# Wireless_thermometer_BLE_module.net
KiCad netlist of a schematic drawn in Altium Designer
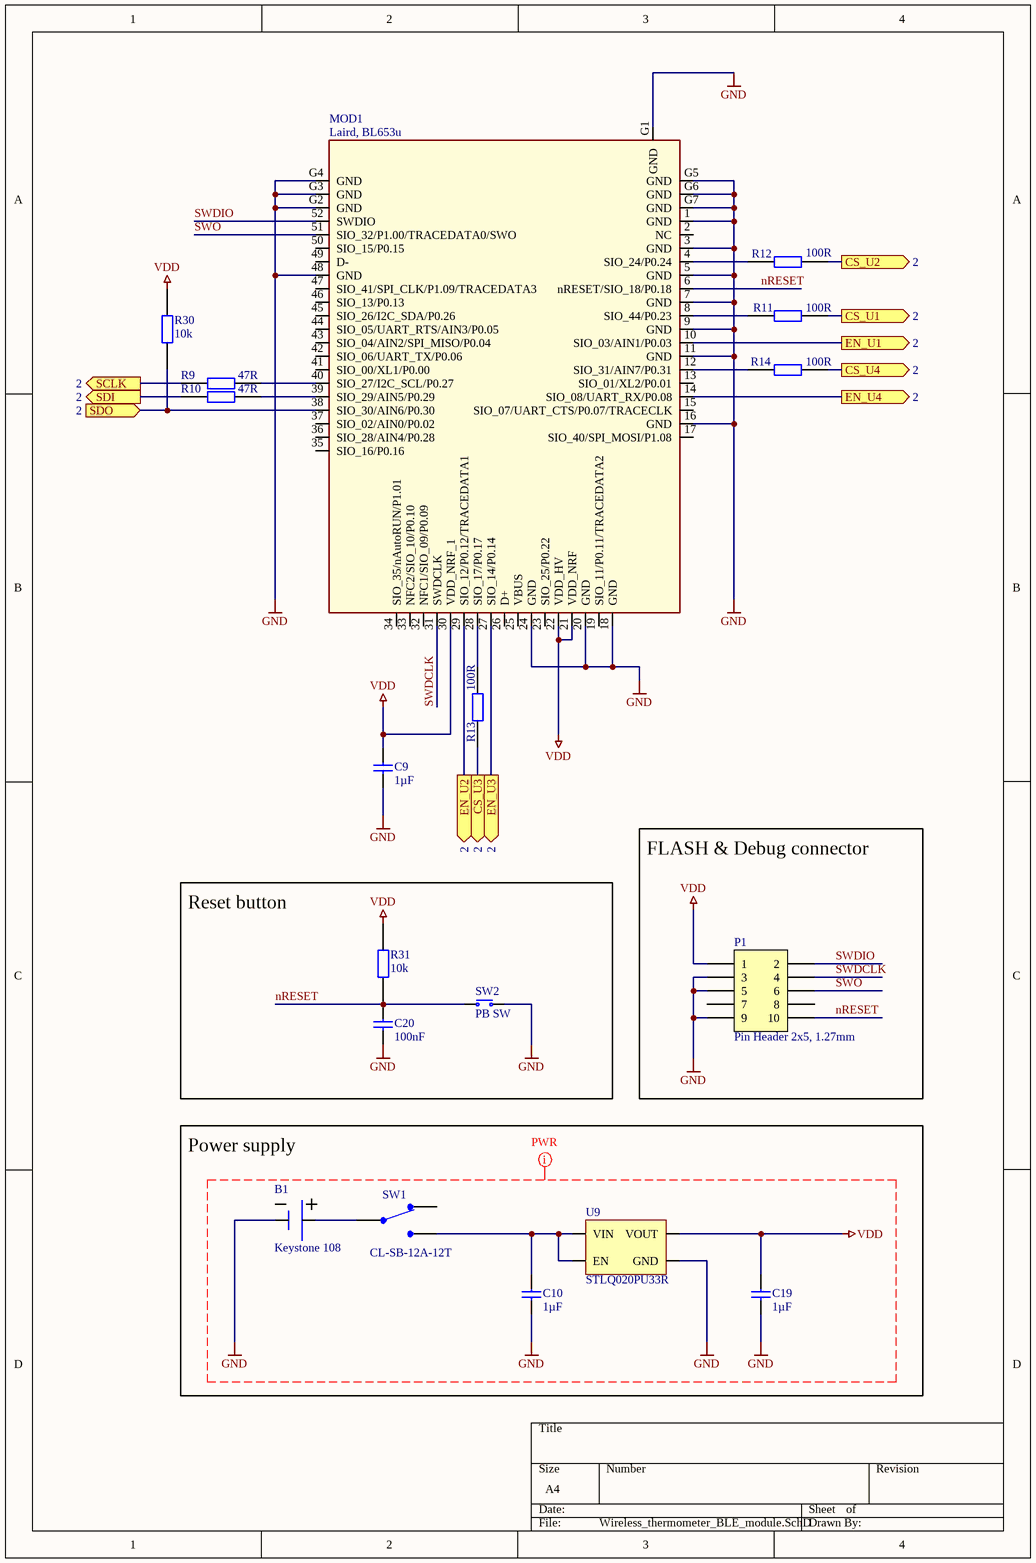
[diagram p0: Wireless_thermometer_BLE_module.SchDoc]

(export (version "E")
  (design (tool "Eeschema 10.0.6"))
  (components
    (comp (ref "B1")
      (value "Keystone 108")
      (footprint "Keystone 108")
      (description "Tip Plg 108 Phe Bagged NKL#9HHS108")
      (fields
        (field (name "MANUFACTURER") "Keystone Electronics")
        (field (name "MANUFACTURER PART NUMBER") "108")
      )
      (libsource (lib "Remote_thermometer") (part "Keystone 108"))
    )
    (comp (ref "C9")
      (value "1µF")
      (footprint "CAPC1005X04L")
      (description "Capacitor, X7R, ±10%")
      (fields (field (name "PART NUMBER") "C0402-1µ0") (field (name "PUBLISHER") "Nordic Semiconductor"))
      (libsource (lib "Remote_thermometer") (part "CAP_0402"))
    )
    (comp (ref "C10")
      (value "1µF")
      (footprint "CAPC1005X04L")
      (description "Capacitor, X7R, ±10%")
      (fields (field (name "PART NUMBER") "C0402-1µ0") (field (name "PUBLISHER") "Nordic Semiconductor"))
      (libsource (lib "Remote_thermometer") (part "CAP_0402"))
    )
    (comp (ref "C19")
      (value "1µF")
      (footprint "CAPC1005X04L")
      (description "Capacitor, X7R, ±10%")
      (fields (field (name "PART NUMBER") "C0402-1µ0") (field (name "PUBLISHER") "Nordic Semiconductor"))
      (libsource (lib "Remote_thermometer") (part "CAP_0402"))
    )
    (comp (ref "C20")
      (value "100nF")
      (footprint "CAPC1005X04L")
      (description "Capacitor, X7R, ±10%")
      (fields (field (name "PART NUMBER") "C0402-1µ0") (field (name "PUBLISHER") "Nordic Semiconductor"))
      (libsource (lib "Remote_thermometer") (part "CAP_0402"))
    )
    (comp (ref "MOD1")
      (value "Laird, BL653u")
      (footprint "Laird, BL653u")
      (description "BL653µ Integrated Antenna module, 453-00059")
      (fields (field (name "MANUFACTURER PART NUMBER") "453-00059") (field (name "MANUFACTURER") "Laird"))
      (libsource (lib "Remote_thermometer") (part "Laird, BL653u"))
    )
    (comp (ref "P1")
      (value "Pin Header 2x5, 1.27mm")
      (footprint "HDR_2x5-SMD-1.27mm-K")
      (description "Pin Header 2x5, 1.27mm (50mil), SMD, Keying Shroud")
      (fields
        (field (name "PART NUMBER") "Pin Header 2x5 SMD, 1.27mm, KS")
        (field (name "MANUFACTURER") "W-CON")
        (field (name "PUBLISHER") "Nordic Semiconductor")
      )
      (libsource (lib "Remote_thermometer") (part "Pin Header 2x5 SMD, 1.27mm, KS"))
    )
    (comp (ref "R9")
      (value "47R")
      (footprint "RESC1005X04L")
      (description "Resistor")
      (fields (field (name "PART NUMBER") "R0603-430R") (field (name "PUBLISHER") "Nordic Semiconductor"))
      (libsource (lib "Remote_thermometer") (part "RES_0402"))
    )
    (comp (ref "R10")
      (value "47R")
      (footprint "RESC1005X04L")
      (description "Resistor")
      (fields (field (name "PART NUMBER") "R0603-430R") (field (name "PUBLISHER") "Nordic Semiconductor"))
      (libsource (lib "Remote_thermometer") (part "RES_0402"))
    )
    (comp (ref "R11")
      (value "100R")
      (footprint "RESC1005X04L")
      (description "Resistor")
      (fields (field (name "PART NUMBER") "R0603-430R") (field (name "PUBLISHER") "Nordic Semiconductor"))
      (libsource (lib "Remote_thermometer") (part "RES_0402"))
    )
    (comp (ref "R12")
      (value "100R")
      (footprint "RESC1005X04L")
      (description "Resistor")
      (fields (field (name "PART NUMBER") "R0603-430R") (field (name "PUBLISHER") "Nordic Semiconductor"))
      (libsource (lib "Remote_thermometer") (part "RES_0402"))
    )
    (comp (ref "R13")
      (value "100R")
      (footprint "RESC1005X04L")
      (description "Resistor")
      (fields (field (name "PART NUMBER") "R0603-430R") (field (name "PUBLISHER") "Nordic Semiconductor"))
      (libsource (lib "Remote_thermometer") (part "RES_0402"))
    )
    (comp (ref "R14")
      (value "100R")
      (footprint "RESC1005X04L")
      (description "Resistor")
      (fields (field (name "PART NUMBER") "R0603-430R") (field (name "PUBLISHER") "Nordic Semiconductor"))
      (libsource (lib "Remote_thermometer") (part "RES_0402"))
    )
    (comp (ref "R30")
      (value "10k")
      (footprint "RESC1005X04L")
      (description "Resistor")
      (fields (field (name "PART NUMBER") "R0603-430R") (field (name "PUBLISHER") "Nordic Semiconductor"))
      (libsource (lib "Remote_thermometer") (part "RES_0402"))
    )
    (comp (ref "R31")
      (value "10k")
      (footprint "RESC1005X04L")
      (description "Resistor")
      (fields (field (name "PART NUMBER") "R0603-430R") (field (name "PUBLISHER") "Nordic Semiconductor"))
      (libsource (lib "Remote_thermometer") (part "RES_0402"))
    )
    (comp (ref "SW1")
      (value "CL-SB-12A-12T")
      (footprint "CL-SB-12A-12T")
      (description "Slide Switch, 2 Positions, SPDT, Latched, 0.2A, 12VDC, Solder Terminal, Through Hole-right Angle")
      (fields (field (name "MANUFACTURER") "Nidec Copal"))
      (libsource (lib "Remote_thermometer") (part "CL-SB-12A-12T"))
    )
    (comp (ref "SW2")
      (value "PB SW")
      (footprint "C&K_PTS810")
      (description "Tactile Switch, SPNO, SMD, 260gf, 4.2x3.2x2.5mm")
      (fields
        (field (name "PART NUMBER") "PTS810 SJK 250 SMTR LFS")
        (field (name "MANUFACTURER") "C&K Components")
        (field (name "PUBLISHER") "Nordic Semiconductor")
      )
      (libsource (lib "Remote_thermometer") (part "PTS810 SJK 250 SMTR LFS"))
    )
    (comp (ref "U9")
      (value "STLQ020PU33R")
      (footprint "STLQ020PU33R")
      (description "Ldo, Fixed, 3.3V, 0.2A, -40 to 125DEG C;")
      (fields (field (name "MANUFACTURER") "STMicroelectronics"))
      (libsource (lib "Remote_thermometer") (part "STLQ020PU33R"))
    )
  )
  (nets
    (net (code "1") (name "/CS_U1") (class "Default")
      (node (ref "R11") (pin "2") (pinfunction "2_2") (pintype "passive"))
    )
    (net (code "2") (name "/CS_U2") (class "Default")
      (node (ref "R12") (pin "2") (pinfunction "2_2") (pintype "passive"))
    )
    (net (code "3") (name "/CS_U3") (class "Default")
      (node (ref "R13") (pin "2") (pinfunction "2_2") (pintype "passive"))
    )
    (net (code "4") (name "/CS_U4") (class "Default")
      (node (ref "R14") (pin "2") (pinfunction "2_2") (pintype "passive"))
    )
    (net (code "5") (name "/EN_U1") (class "Default")
      (node (ref "MOD1") (pin "10") (pinfunction "SIO_03/AIN1/P0.03_10") (pintype "passive"))
    )
    (net (code "6") (name "/EN_U2") (class "Default")
      (node (ref "MOD1") (pin "29") (pinfunction "SIO_12/P0.12/TRACEDATA1_29") (pintype "passive"))
    )
    (net (code "7") (name "/EN_U3") (class "Default")
      (node (ref "MOD1") (pin "27") (pinfunction "SIO_14/P0.14_27") (pintype "passive"))
    )
    (net (code "8") (name "/EN_U4") (class "Default")
      (node (ref "MOD1") (pin "14") (pinfunction "SIO_08/UART_RX/P0.08_14") (pintype "passive"))
    )
    (net (code "9") (name "/SCLK") (class "Default")
      (node (ref "R9") (pin "1") (pinfunction "1_1") (pintype "passive"))
    )
    (net (code "10") (name "/SDI") (class "Default")
      (node (ref "R10") (pin "1") (pinfunction "1_1") (pintype "passive"))
    )
    (net (code "11") (name "/SDO") (class "Default")
      (node (ref "MOD1") (pin "38") (pinfunction "SIO_30/AIN6/P0.30_38") (pintype "passive"))
      (node (ref "R30") (pin "1") (pinfunction "1_1") (pintype "passive"))
    )
    (net (code "12") (name "/SWDCLK") (class "Default")
      (node (ref "MOD1") (pin "31") (pinfunction "SWDCLK_31") (pintype "passive"))
      (node (ref "P1") (pin "4") (pinfunction "4_4") (pintype "passive"))
    )
    (net (code "13") (name "/SWDIO") (class "Default")
      (node (ref "MOD1") (pin "52") (pinfunction "SWDIO_52") (pintype "passive"))
      (node (ref "P1") (pin "2") (pinfunction "2_2") (pintype "passive"))
    )
    (net (code "14") (name "/SWO") (class "Default")
      (node (ref "MOD1") (pin "51") (pinfunction "SIO_32/P1.00/TRACEDATA0/SWO_51") (pintype "passive"))
      (node (ref "P1") (pin "6") (pinfunction "6_6") (pintype "passive"))
    )
    (net (code "15") (name "/nRESET") (class "Default")
      (node (ref "C20") (pin "2") (pinfunction "2_2") (pintype "passive"))
      (node (ref "MOD1") (pin "6") (pinfunction "nRESET/SIO_18/P0.18_6") (pintype "passive"))
      (node (ref "P1") (pin "10") (pinfunction "10_10") (pintype "passive"))
      (node (ref "R31") (pin "1") (pinfunction "1_1") (pintype "passive"))
      (node (ref "SW2") (pin "2") (pinfunction "COM_2") (pintype "passive"))
    )
    (net (code "16") (name "GND") (class "Default")
      (node (ref "B1") (pin "2") (pinfunction "2_2") (pintype "passive"))
      (node (ref "C10") (pin "1") (pinfunction "1_1") (pintype "passive"))
      (node (ref "C19") (pin "1") (pinfunction "1_1") (pintype "passive"))
      (node (ref "C20") (pin "1") (pinfunction "1_1") (pintype "passive"))
      (node (ref "C9") (pin "1") (pinfunction "1_1") (pintype "passive"))
      (node (ref "MOD1") (pin "1") (pinfunction "GND_1") (pintype "passive"))
      (node (ref "MOD1") (pin "11") (pinfunction "GND_11") (pintype "passive"))
      (node (ref "MOD1") (pin "16") (pinfunction "GND_16") (pintype "passive"))
      (node (ref "MOD1") (pin "18") (pinfunction "GND_18") (pintype "passive"))
      (node (ref "MOD1") (pin "20") (pinfunction "GND_20") (pintype "passive"))
      (node (ref "MOD1") (pin "24") (pinfunction "GND_24") (pintype "passive"))
      (node (ref "MOD1") (pin "3") (pinfunction "GND_3") (pintype "passive"))
      (node (ref "MOD1") (pin "48") (pinfunction "GND_48") (pintype "passive"))
      (node (ref "MOD1") (pin "5") (pinfunction "GND_5") (pintype "passive"))
      (node (ref "MOD1") (pin "7") (pinfunction "GND_7") (pintype "passive"))
      (node (ref "MOD1") (pin "9") (pinfunction "GND_9") (pintype "passive"))
      (node (ref "MOD1") (pin "G1") (pinfunction "GND_G1") (pintype "passive"))
      (node (ref "MOD1") (pin "G2") (pinfunction "GND_G2") (pintype "passive"))
      (node (ref "MOD1") (pin "G3") (pinfunction "GND_G3") (pintype "passive"))
      (node (ref "MOD1") (pin "G4") (pinfunction "GND_G4") (pintype "passive"))
      (node (ref "MOD1") (pin "G5") (pinfunction "GND_G5") (pintype "passive"))
      (node (ref "MOD1") (pin "G6") (pinfunction "GND_G6") (pintype "passive"))
      (node (ref "MOD1") (pin "G7") (pinfunction "GND_G7") (pintype "passive"))
      (node (ref "P1") (pin "3") (pinfunction "3_3") (pintype "passive"))
      (node (ref "P1") (pin "5") (pinfunction "5_5") (pintype "passive"))
      (node (ref "P1") (pin "9") (pinfunction "9_9") (pintype "passive"))
      (node (ref "SW2") (pin "1") (pinfunction "N.O_1") (pintype "passive"))
      (node (ref "U9") (pin "3") (pinfunction "GND_3") (pintype "passive"))
    )
    (net (code "17") (name "Net-(B1-Pad1)") (class "Default")
      (node (ref "B1") (pin "1") (pinfunction "1_1") (pintype "passive"))
      (node (ref "SW1") (pin "2") (pinfunction "2_2") (pintype "passive"))
    )
    (net (code "18") (name "Net-(MOD1-SIO_17{slash}P0.17)") (class "Default")
      (node (ref "MOD1") (pin "28") (pinfunction "SIO_17/P0.17_28") (pintype "passive"))
      (node (ref "R13") (pin "1") (pinfunction "1_1") (pintype "passive"))
    )
    (net (code "19") (name "Net-(MOD1-SIO_24{slash}P0.24)") (class "Default")
      (node (ref "MOD1") (pin "4") (pinfunction "SIO_24/P0.24_4") (pintype "passive"))
      (node (ref "R12") (pin "1") (pinfunction "1_1") (pintype "passive"))
    )
    (net (code "20") (name "Net-(MOD1-SIO_27{slash}I2C_SCL{slash}P0.27)") (class "Default")
      (node (ref "MOD1") (pin "40") (pinfunction "SIO_27/I2C_SCL/P0.27_40") (pintype "passive"))
      (node (ref "R9") (pin "2") (pinfunction "2_2") (pintype "passive"))
    )
    (net (code "21") (name "Net-(MOD1-SIO_29{slash}AIN5{slash}P0.29)") (class "Default")
      (node (ref "MOD1") (pin "39") (pinfunction "SIO_29/AIN5/P0.29_39") (pintype "passive"))
      (node (ref "R10") (pin "2") (pinfunction "2_2") (pintype "passive"))
    )
    (net (code "22") (name "Net-(MOD1-SIO_31{slash}AIN7{slash}P0.31)") (class "Default")
      (node (ref "MOD1") (pin "12") (pinfunction "SIO_31/AIN7/P0.31_12") (pintype "passive"))
      (node (ref "R14") (pin "1") (pinfunction "1_1") (pintype "passive"))
    )
    (net (code "23") (name "Net-(MOD1-SIO_44{slash}P0.23)") (class "Default")
      (node (ref "MOD1") (pin "8") (pinfunction "SIO_44/P0.23_8") (pintype "passive"))
      (node (ref "R11") (pin "1") (pinfunction "1_1") (pintype "passive"))
    )
    (net (code "24") (name "Net-(U9-EN)") (class "Default")
      (node (ref "C10") (pin "2") (pinfunction "2_2") (pintype "passive"))
      (node (ref "SW1") (pin "3") (pinfunction "3_3") (pintype "passive"))
      (node (ref "U9") (pin "4") (pinfunction "EN_4") (pintype "passive"))
      (node (ref "U9") (pin "6") (pinfunction "VIN_6") (pintype "passive"))
    )
    (net (code "25") (name "VDD") (class "Default")
      (node (ref "C19") (pin "2") (pinfunction "2_2") (pintype "passive"))
      (node (ref "C9") (pin "2") (pinfunction "2_2") (pintype "passive"))
      (node (ref "MOD1") (pin "21") (pinfunction "VDD_NRF_21") (pintype "passive"))
      (node (ref "MOD1") (pin "22") (pinfunction "VDD_HV_22") (pintype "passive"))
      (node (ref "MOD1") (pin "30") (pinfunction "VDD_NRF_1_30") (pintype "passive"))
      (node (ref "P1") (pin "1") (pinfunction "1_1") (pintype "passive"))
      (node (ref "R30") (pin "2") (pinfunction "2_2") (pintype "passive"))
      (node (ref "R31") (pin "2") (pinfunction "2_2") (pintype "passive"))
      (node (ref "U9") (pin "1") (pinfunction "VOUT_1") (pintype "passive"))
    )
    (net (code "26") (name "unconnected-(MOD1-D+-Pad26)") (class "Default")
      (node (ref "MOD1") (pin "26") (pinfunction "D+_26") (pintype "passive"))
    )
    (net (code "27") (name "unconnected-(MOD1-D--Pad49)") (class "Default")
      (node (ref "MOD1") (pin "49") (pinfunction "D-_49") (pintype "passive"))
    )
    (net (code "28") (name "unconnected-(MOD1-NC-Pad2)") (class "Default")
      (node (ref "MOD1") (pin "2") (pinfunction "NC_2") (pintype "passive"))
    )
    (net (code "29") (name "unconnected-(MOD1-NFC1{slash}SIO_09{slash}P0.09-Pad32)") (class "Default")
      (node (ref "MOD1") (pin "32") (pinfunction "NFC1/SIO_09/P0.09_32") (pintype "passive"))
    )
    (net (code "30") (name "unconnected-(MOD1-NFC2{slash}SIO_10{slash}P0.10-Pad33)") (class "Default")
      (node (ref "MOD1") (pin "33") (pinfunction "NFC2/SIO_10/P0.10_33") (pintype "passive"))
    )
    (net (code "31") (name "unconnected-(MOD1-SIO_00{slash}XL1{slash}P0.00-Pad41)") (class "Default")
      (node (ref "MOD1") (pin "41") (pinfunction "SIO_00/XL1/P0.00_41") (pintype "passive"))
    )
    (net (code "32") (name "unconnected-(MOD1-SIO_01{slash}XL2{slash}P0.01-Pad13)") (class "Default")
      (node (ref "MOD1") (pin "13") (pinfunction "SIO_01/XL2/P0.01_13") (pintype "passive"))
    )
    (net (code "33") (name "unconnected-(MOD1-SIO_02{slash}AIN0{slash}P0.02-Pad37)") (class "Default")
      (node (ref "MOD1") (pin "37") (pinfunction "SIO_02/AIN0/P0.02_37") (pintype "passive"))
    )
    (net (code "34") (name "unconnected-(MOD1-SIO_04{slash}AIN2{slash}SPI_MISO{slash}P0.04-Pad43)") (class "Default")
      (node (ref "MOD1") (pin "43") (pinfunction "SIO_04/AIN2/SPI_MISO/P0.04_43") (pintype "passive"))
    )
    (net (code "35") (name "unconnected-(MOD1-SIO_05{slash}UART_RTS{slash}AIN3{slash}P0.05-Pad44)") (class "Default")
      (node (ref "MOD1") (pin "44") (pinfunction "SIO_05/UART_RTS/AIN3/P0.05_44") (pintype "passive"))
    )
    (net (code "36") (name "unconnected-(MOD1-SIO_06{slash}UART_TX{slash}P0.06-Pad42)") (class "Default")
      (node (ref "MOD1") (pin "42") (pinfunction "SIO_06/UART_TX/P0.06_42") (pintype "passive"))
    )
    (net (code "37") (name "unconnected-(MOD1-SIO_07{slash}UART_CTS{slash}P0.07{slash}TRACECLK-Pad15)") (class "Default")
      (node (ref "MOD1") (pin "15") (pinfunction "SIO_07/UART_CTS/P0.07/TRACECLK_15") (pintype "passive"))
    )
    (net (code "38") (name "unconnected-(MOD1-SIO_11{slash}P0.11{slash}TRACEDATA2-Pad19)") (class "Default")
      (node (ref "MOD1") (pin "19") (pinfunction "SIO_11/P0.11/TRACEDATA2_19") (pintype "passive"))
    )
    (net (code "39") (name "unconnected-(MOD1-SIO_13{slash}P0.13-Pad46)") (class "Default")
      (node (ref "MOD1") (pin "46") (pinfunction "SIO_13/P0.13_46") (pintype "passive"))
    )
    (net (code "40") (name "unconnected-(MOD1-SIO_15{slash}P0.15-Pad50)") (class "Default")
      (node (ref "MOD1") (pin "50") (pinfunction "SIO_15/P0.15_50") (pintype "passive"))
    )
    (net (code "41") (name "unconnected-(MOD1-SIO_16{slash}P0.16-Pad35)") (class "Default")
      (node (ref "MOD1") (pin "35") (pinfunction "SIO_16/P0.16_35") (pintype "passive"))
    )
    (net (code "42") (name "unconnected-(MOD1-SIO_25{slash}P0.22-Pad23)") (class "Default")
      (node (ref "MOD1") (pin "23") (pinfunction "SIO_25/P0.22_23") (pintype "passive"))
    )
    (net (code "43") (name "unconnected-(MOD1-SIO_26{slash}I2C_SDA{slash}P0.26-Pad45)") (class "Default")
      (node (ref "MOD1") (pin "45") (pinfunction "SIO_26/I2C_SDA/P0.26_45") (pintype "passive"))
    )
    (net (code "44") (name "unconnected-(MOD1-SIO_28{slash}AIN4{slash}P0.28-Pad36)") (class "Default")
      (node (ref "MOD1") (pin "36") (pinfunction "SIO_28/AIN4/P0.28_36") (pintype "passive"))
    )
    (net (code "45") (name "unconnected-(MOD1-SIO_35{slash}nAutoRUN{slash}P1.01-Pad34)") (class "Default")
      (node (ref "MOD1") (pin "34") (pinfunction "SIO_35/nAutoRUN/P1.01_34") (pintype "passive"))
    )
    (net (code "46") (name "unconnected-(MOD1-SIO_40{slash}SPI_MOSI{slash}P1.08-Pad17)") (class "Default")
      (node (ref "MOD1") (pin "17") (pinfunction "SIO_40/SPI_MOSI/P1.08_17") (pintype "passive"))
    )
    (net (code "47") (name "unconnected-(MOD1-SIO_41{slash}SPI_CLK{slash}P1.09{slash}TRACEDATA3-Pad47)") (class "Default")
      (node (ref "MOD1") (pin "47") (pinfunction "SIO_41/SPI_CLK/P1.09/TRACEDATA3_47") (pintype "passive"))
    )
    (net (code "48") (name "unconnected-(MOD1-VBUS-Pad25)") (class "Default")
      (node (ref "MOD1") (pin "25") (pinfunction "VBUS_25") (pintype "passive"))
    )
    (net (code "49") (name "unconnected-(P1-Pad7)") (class "Default")
      (node (ref "P1") (pin "7") (pinfunction "7_7") (pintype "passive"))
    )
    (net (code "50") (name "unconnected-(P1-Pad8)") (class "Default")
      (node (ref "P1") (pin "8") (pinfunction "8_8") (pintype "passive"))
    )
    (net (code "51") (name "unconnected-(SW1-Pad1)") (class "Default")
      (node (ref "SW1") (pin "1") (pinfunction "1_1") (pintype "passive"))
    )
  )
)
